# Detector.net
KiCad netlist of a schematic drawn in Altium Designer
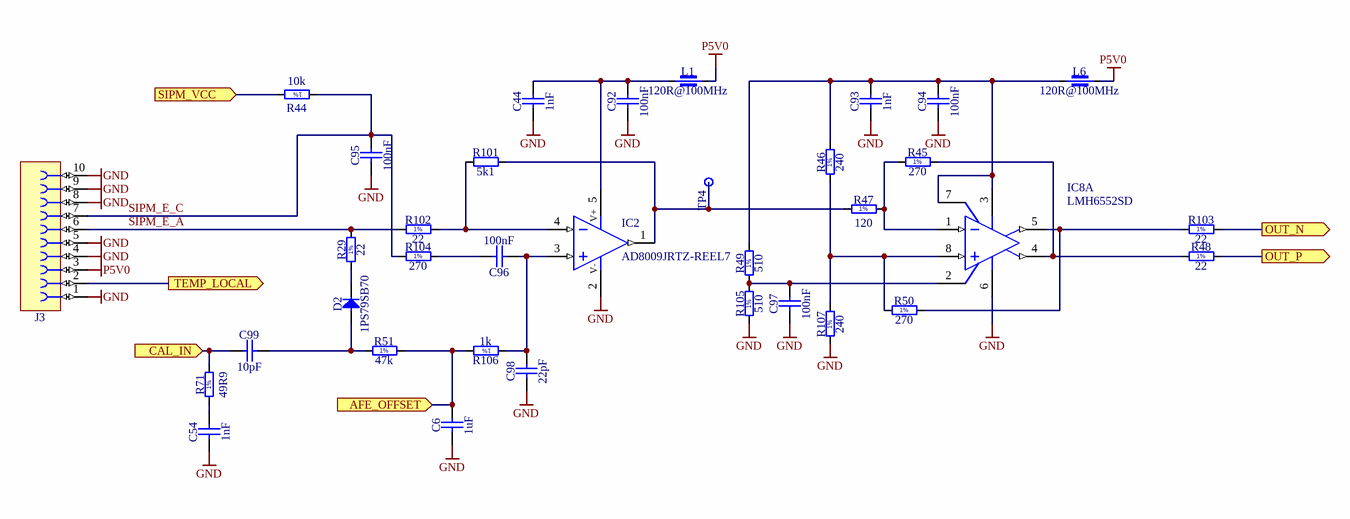
[diagram p0: Detector.SchDoc]

(export (version "E")
  (design (tool "Eeschema 10.0.6"))
  (components
    (comp (ref "C6")
      (value "1uF")
      (footprint "CAPC1608X87N")
      (description "Non-polarised capacitor")
      (fields
        (field (name "PART NUMBER") "CC0603_1UF_16V_10%_X7R")
        (field (name "VOLTAGE") "16V")
        (field (name "AUTHOR") "CERN DEM JLC")
      )
      (libsource (lib "Capacitors") (part "Capacitor - non polarized"))
    )
    (comp (ref "C44")
      (value "1nF")
      (footprint "CAPC1005X55N")
      (description "Non-polarised capacitor")
      (fields
        (field (name "PART NUMBER") "CC0402_1NF_50V_5%_C0G")
        (field (name "VOLTAGE") "50V")
        (field (name "AUTHOR") "CERN DEM BC")
      )
      (libsource (lib "Capacitors") (part "Capacitor - non polarized"))
    )
    (comp (ref "C54")
      (value "1nF")
      (footprint "CAPC1005X55N")
      (description "Non-polarised capacitor")
      (fields
        (field (name "PART NUMBER") "CC0402_1NF_50V_5%_C0G")
        (field (name "VOLTAGE") "50V")
        (field (name "AUTHOR") "CERN DEM BC")
      )
      (libsource (lib "Capacitors") (part "Capacitor - non polarized"))
    )
    (comp (ref "C92")
      (value "100nF")
      (footprint "CAPC1005X55N")
      (description "Non-polarised capacitor")
      (fields
        (field (name "PART NUMBER") "CC0402_100NF_16V_10%_X7R")
        (field (name "VOLTAGE") "16V")
        (field (name "AUTHOR") "CERN DEM JLC")
      )
      (libsource (lib "Capacitors") (part "Capacitor - non polarized"))
    )
    (comp (ref "C93")
      (value "1nF")
      (footprint "CAPC1005X55N")
      (description "Non-polarised capacitor")
      (fields
        (field (name "PART NUMBER") "CC0402_1NF_50V_5%_C0G")
        (field (name "VOLTAGE") "50V")
        (field (name "AUTHOR") "CERN DEM BC")
      )
      (libsource (lib "Capacitors") (part "Capacitor - non polarized"))
    )
    (comp (ref "C94")
      (value "100nF")
      (footprint "CAPC1005X55N")
      (description "Non-polarised capacitor")
      (fields
        (field (name "PART NUMBER") "CC0402_100NF_16V_10%_X7R")
        (field (name "VOLTAGE") "16V")
        (field (name "AUTHOR") "CERN DEM JLC")
      )
      (libsource (lib "Capacitors") (part "Capacitor - non polarized"))
    )
    (comp (ref "C95")
      (value "100nF")
      (footprint "CAPC1608X90N")
      (description "Non-polarised capacitor")
      (fields
        (field (name "PART NUMBER") "CC0603_100NF_100V_10%_X7R")
        (field (name "VOLTAGE") "100V")
        (field (name "AUTHOR") "CERN DEM JLC")
      )
      (libsource (lib "Capacitors") (part "Capacitor - non polarized"))
    )
    (comp (ref "C96")
      (value "100nF")
      (footprint "CAPC1608X90N")
      (description "Non-polarised capacitor")
      (fields
        (field (name "PART NUMBER") "CC0603_100NF_100V_10%_X7R")
        (field (name "VOLTAGE") "100V")
        (field (name "AUTHOR") "CERN DEM JLC")
      )
      (libsource (lib "Capacitors") (part "Capacitor - non polarized"))
    )
    (comp (ref "C97")
      (value "100nF")
      (footprint "CAPC1005X55N")
      (description "Non-polarised capacitor")
      (fields
        (field (name "PART NUMBER") "CC0402_100NF_16V_10%_X7R")
        (field (name "VOLTAGE") "16V")
        (field (name "AUTHOR") "CERN DEM JLC")
      )
      (libsource (lib "Capacitors") (part "Capacitor - non polarized"))
    )
    (comp (ref "C98")
      (value "22pF")
      (footprint "CAPC1005X55N")
      (description "Non-polarised capacitor")
      (fields
        (field (name "PART NUMBER") "CC0402_22PF_50V_5%_C0G")
        (field (name "VOLTAGE") "50V")
        (field (name "AUTHOR") "CERN DEM JLC")
      )
      (libsource (lib "Capacitors") (part "Capacitor - non polarized"))
    )
    (comp (ref "C99")
      (value "10pF")
      (footprint "CAPC1608X87N")
      (description "Non-polarised capacitor")
      (fields
        (field (name "PART NUMBER") "CC0603_10PF_50V_5%_NP0")
        (field (name "VOLTAGE") "50V")
        (field (name "AUTHOR") "CERN DEM JLC")
      )
      (libsource (lib "Capacitors") (part "Capacitor - non polarized"))
    )
    (comp (ref "D2")
      (value "1PS79SB70")
      (footprint "SODFL1608X65N")
      (description "Diode")
      (fields (field (name "VOLTAGE") "70V") (field (name "POWER") "70mA") (field (name "AUTHOR") "GK"))
      (libsource (lib "Diodes") (part "D_1PS79SB70"))
    )
    (comp (ref "IC2")
      (value "AD8009JRTZ-REEL7")
      (footprint "SOT95P280X145-5N")
      (description "Operational Amplifier")
      (fields (field (name "MANUFACTURER") "ANALOG DEVICES") (field (name "AUTHOR") "CERN DEM JLC"))
      (libsource (lib "ICs And Semiconductors") (part "Operational Amplifier Type7"))
    )
    (comp (ref "IC8")
      (value "LMH6552SD")
      (footprint "SDA08C")
      (description "1.5 GHz Fully Differential Amplifier, 8-pin LLP")
      (fields (field (name "MANUFACTURER") "National Semiconductor"))
      (libsource (lib "Altium Content Vault") (part "AMP-DIFA-LMH6552-9"))
    )
    (comp (ref "J3")
      (value "FFC/FPC")
      (footprint "MOLEX_52745-1097")
      (description "Connector 10 Female")
      (fields
        (field (name "PART NUMBER") "MOLEX_52745-1097")
        (field (name "MANUFACTURER") "MOLEX")
        (field (name "AUTHOR") "CERN DEM JLC")
      )
      (libsource (lib "Connectors") (part "Connector 10 Female"))
    )
    (comp (ref "L1")
      (value "120R@100MHz")
      (footprint "INDC1005X55N")
      (fields
        (field (name "PART NUMBER") "IND0402_MURATA_BLM15PX121SN1D")
        (field (name "POWER") "2A")
        (field (name "TOLERANCE") "±25%")
        (field (name "AUTHOR") "CERN DEM JMW")
      )
      (libsource (lib "Inductors & Transformers") (part "Ferrite Bead"))
    )
    (comp (ref "L6")
      (value "120R@100MHz")
      (footprint "INDC1005X55N")
      (fields
        (field (name "PART NUMBER") "IND0402_MURATA_BLM15PX121SN1D")
        (field (name "POWER") "2A")
        (field (name "TOLERANCE") "±25%")
        (field (name "AUTHOR") "CERN DEM JMW")
      )
      (libsource (lib "Inductors & Transformers") (part "Ferrite Bead"))
    )
    (comp (ref "R29")
      (value "22")
      (footprint "RESC1608X55N")
      (description "Resistor - 1%")
      (fields
        (field (name "PART NUMBER") "R0603_22R_1%_0.1W_100PPM")
        (field (name "POWER") "0.1W")
        (field (name "AUTHOR") "CERN DEM JLC")
      )
      (libsource (lib "Resistors") (part "Resistor - 1%"))
    )
    (comp (ref "R44")
      (value "10k")
      (footprint "RESC1005X40N")
      (description "Resistor - 1%")
      (fields
        (field (name "PART NUMBER") "R0402_10K_1%_0.0625W_100PPM")
        (field (name "POWER") "0.0625W")
        (field (name "AUTHOR") "CERN DEM JLC")
      )
      (libsource (lib "Resistors") (part "Resistor - 1%"))
    )
    (comp (ref "R45")
      (value "270")
      (footprint "RESC1005X40N")
      (description "Resistor - 1%")
      (fields
        (field (name "PART NUMBER") "R0402_270R_1%_0.0625W_100PPM")
        (field (name "POWER") "0.0625W")
        (field (name "AUTHOR") "CERN DEM JLC")
      )
      (libsource (lib "Resistors") (part "Resistor - 1%"))
    )
    (comp (ref "R46")
      (value "240")
      (footprint "RESC1005X40N")
      (description "Resistor - 1%")
      (fields
        (field (name "PART NUMBER") "R0402_240R_1%_0.0625W_100PPM")
        (field (name "POWER") "0.0625W")
        (field (name "AUTHOR") "CERN DEM JLC")
      )
      (libsource (lib "Resistors") (part "Resistor - 1%"))
    )
    (comp (ref "R47")
      (value "120")
      (footprint "RESC1005X40N")
      (description "Resistor - 1%")
      (fields
        (field (name "PART NUMBER") "R0402_120R_1%_0.0625W_100PPM")
        (field (name "POWER") "0.0625W")
        (field (name "AUTHOR") "CERN DEM JLC")
      )
      (libsource (lib "Resistors") (part "Resistor - 1%"))
    )
    (comp (ref "R48")
      (value "22")
      (footprint "RESC1608X55N")
      (description "Resistor - 1%")
      (fields
        (field (name "PART NUMBER") "R0603_22R_1%_0.1W_100PPM")
        (field (name "POWER") "0.1W")
        (field (name "AUTHOR") "CERN DEM JLC")
      )
      (libsource (lib "Resistors") (part "Resistor - 1%"))
    )
    (comp (ref "R49")
      (value "510")
      (footprint "RESC1005X40N")
      (description "Resistor - 1%")
      (fields
        (field (name "PART NUMBER") "R0402_510R_1%_0.0625W_100PPM")
        (field (name "POWER") "0.0625W")
        (field (name "AUTHOR") "CERN DEM JLC")
      )
      (libsource (lib "Resistors") (part "Resistor - 1%"))
    )
    (comp (ref "R50")
      (value "270")
      (footprint "RESC1005X40N")
      (description "Resistor - 1%")
      (fields
        (field (name "PART NUMBER") "R0402_270R_1%_0.0625W_100PPM")
        (field (name "POWER") "0.0625W")
        (field (name "AUTHOR") "CERN DEM JLC")
      )
      (libsource (lib "Resistors") (part "Resistor - 1%"))
    )
    (comp (ref "R51")
      (value "47k")
      (footprint "RESC1005X40N")
      (description "Resistor - 1%")
      (fields
        (field (name "PART NUMBER") "R0402_47K_1%_0.0625W_100PPM")
        (field (name "POWER") "0.0625W")
        (field (name "AUTHOR") "CERN DEM JLC")
      )
      (libsource (lib "Resistors") (part "Resistor - 1%"))
    )
    (comp (ref "R71")
      (value "49R9")
      (footprint "RESC1005X40N")
      (description "Resistor - 1%")
      (fields
        (field (name "PART NUMBER") "R0402_49R9_1%_0.0625W_100PPM")
        (field (name "POWER") "0.0625W")
        (field (name "AUTHOR") "CERN DEM JLC")
      )
      (libsource (lib "Resistors") (part "Resistor - 1%"))
    )
    (comp (ref "R101")
      (value "5k1")
      (footprint "RESC1005X40N")
      (description "Resistor - 1%")
      (fields
        (field (name "PART NUMBER") "R0402_5K1_1%_0.0625W_100PPM")
        (field (name "POWER") "0.0625W")
        (field (name "AUTHOR") "CERN DEM JLC")
      )
      (libsource (lib "") (part "Resistor - 1%_1"))
    )
    (comp (ref "R102")
      (value "22")
      (footprint "RESC1608X55N")
      (description "Resistor - 1%")
      (fields
        (field (name "PART NUMBER") "R0603_22R_1%_0.1W_100PPM")
        (field (name "POWER") "0.1W")
        (field (name "AUTHOR") "CERN DEM JLC")
      )
      (libsource (lib "Resistors") (part "Resistor - 1%"))
    )
    (comp (ref "R103")
      (value "22")
      (footprint "RESC1608X55N")
      (description "Resistor - 1%")
      (fields
        (field (name "PART NUMBER") "R0603_22R_1%_0.1W_100PPM")
        (field (name "POWER") "0.1W")
        (field (name "AUTHOR") "CERN DEM JLC")
      )
      (libsource (lib "Resistors") (part "Resistor - 1%"))
    )
    (comp (ref "R104")
      (value "270")
      (footprint "RESC1005X40N")
      (description "Resistor - 1%")
      (fields
        (field (name "PART NUMBER") "R0402_270R_1%_0.0625W_100PPM")
        (field (name "POWER") "0.0625W")
        (field (name "AUTHOR") "CERN DEM JLC")
      )
      (libsource (lib "Resistors") (part "Resistor - 1%"))
    )
    (comp (ref "R105")
      (value "510")
      (footprint "RESC1005X40N")
      (description "Resistor - 1%")
      (fields
        (field (name "PART NUMBER") "R0402_510R_1%_0.0625W_100PPM")
        (field (name "POWER") "0.0625W")
        (field (name "AUTHOR") "CERN DEM JLC")
      )
      (libsource (lib "Resistors") (part "Resistor - 1%"))
    )
    (comp (ref "R106")
      (value "1k")
      (footprint "RESC1005X40N")
      (description "Resistor - 1%")
      (fields
        (field (name "PART NUMBER") "R0402_1K_1%_0.0625W_100PPM")
        (field (name "POWER") "0.0625W")
        (field (name "AUTHOR") "CERN DEM JLC")
      )
      (libsource (lib "Resistors") (part "Resistor - 1%"))
    )
    (comp (ref "R107")
      (value "240")
      (footprint "RESC1005X40N")
      (description "Resistor - 1%")
      (fields
        (field (name "PART NUMBER") "R0402_240R_1%_0.0625W_100PPM")
        (field (name "POWER") "0.0625W")
        (field (name "AUTHOR") "CERN DEM JLC")
      )
      (libsource (lib "Resistors") (part "Resistor - 1%"))
    )
    (comp (ref "TP4")
      (value "Test Point")
      (footprint "TPS127")
      (fields (field (name "PART NUMBER") "SMD_PAD_1.27X1.27MM") (field (name "AUTHOR") "CERN DEM JLC"))
      (libsource (lib "Eletro-mechanical") (part "Test Point"))
    )
  )
  (nets
    (net (code "1") (name "/AFE_OFFSET") (class "Default")
      (node (ref "C6") (pin "2") (pinfunction "2_2") (pintype "passive"))
      (node (ref "R106") (pin "2") (pinfunction "2_2") (pintype "passive"))
      (node (ref "R51") (pin "2") (pinfunction "2_2") (pintype "passive"))
    )
    (net (code "2") (name "/CAL_IN") (class "Default")
      (node (ref "C99") (pin "1") (pinfunction "1_1") (pintype "passive"))
      (node (ref "R71") (pin "2") (pinfunction "2_2") (pintype "passive"))
    )
    (net (code "3") (name "/OUT_N") (class "Default")
      (node (ref "R103") (pin "2") (pinfunction "2_2") (pintype "passive"))
    )
    (net (code "4") (name "/OUT_P") (class "Default")
      (node (ref "R48") (pin "2") (pinfunction "2_2") (pintype "passive"))
    )
    (net (code "5") (name "/SIPM_E_A") (class "Default")
      (node (ref "J3") (pin "6") (pinfunction "6_6") (pintype "bidirectional"))
      (node (ref "R102") (pin "1") (pinfunction "1_1") (pintype "passive"))
      (node (ref "R29") (pin "2") (pinfunction "2_2") (pintype "passive"))
    )
    (net (code "6") (name "/SIPM_E_C") (class "Default")
      (node (ref "C95") (pin "2") (pinfunction "2_2") (pintype "passive"))
      (node (ref "J3") (pin "7") (pinfunction "7_7") (pintype "bidirectional"))
      (node (ref "R104") (pin "1") (pinfunction "1_1") (pintype "passive"))
      (node (ref "R44") (pin "1") (pinfunction "1_1") (pintype "passive"))
    )
    (net (code "7") (name "/SIPM_VCC") (class "Default")
      (node (ref "R44") (pin "2") (pinfunction "2_2") (pintype "passive"))
    )
    (net (code "8") (name "/TEMP_LOCAL") (class "Default")
      (node (ref "J3") (pin "2") (pinfunction "2_2") (pintype "bidirectional"))
    )
    (net (code "9") (name "GND") (class "Default")
      (node (ref "C44") (pin "1") (pinfunction "1_1") (pintype "passive"))
      (node (ref "C54") (pin "1") (pinfunction "1_1") (pintype "passive"))
      (node (ref "C6") (pin "1") (pinfunction "1_1") (pintype "passive"))
      (node (ref "C92") (pin "1") (pinfunction "1_1") (pintype "passive"))
      (node (ref "C93") (pin "1") (pinfunction "1_1") (pintype "passive"))
      (node (ref "C94") (pin "1") (pinfunction "1_1") (pintype "passive"))
      (node (ref "C95") (pin "1") (pinfunction "1_1") (pintype "passive"))
      (node (ref "C97") (pin "1") (pinfunction "1_1") (pintype "passive"))
      (node (ref "C98") (pin "1") (pinfunction "1_1") (pintype "passive"))
      (node (ref "IC2") (pin "2") (pinfunction "V-_2") (pintype "power_in"))
      (node (ref "IC8") (pin "6") (pinfunction "V-_6") (pintype "power_in"))
      (node (ref "J3") (pin "1") (pinfunction "1_1") (pintype "bidirectional"))
      (node (ref "J3") (pin "10") (pinfunction "10_10") (pintype "bidirectional"))
      (node (ref "J3") (pin "4") (pinfunction "4_4") (pintype "bidirectional"))
      (node (ref "J3") (pin "5") (pinfunction "5_5") (pintype "bidirectional"))
      (node (ref "J3") (pin "8") (pinfunction "8_8") (pintype "bidirectional"))
      (node (ref "J3") (pin "9") (pinfunction "9_9") (pintype "bidirectional"))
      (node (ref "R105") (pin "1") (pinfunction "1_1") (pintype "passive"))
      (node (ref "R107") (pin "1") (pinfunction "1_1") (pintype "passive"))
    )
    (net (code "10") (name "Net-(C54-Pad2)") (class "Default")
      (node (ref "C54") (pin "2") (pinfunction "2_2") (pintype "passive"))
      (node (ref "R71") (pin "1") (pinfunction "1_1") (pintype "passive"))
    )
    (net (code "11") (name "Net-(C96-Pad2)") (class "Default")
      (node (ref "C96") (pin "2") (pinfunction "2_2") (pintype "passive"))
      (node (ref "R104") (pin "2") (pinfunction "2_2") (pintype "passive"))
    )
    (net (code "12") (name "Net-(D2-A)") (class "Default")
      (node (ref "C99") (pin "2") (pinfunction "2_2") (pintype "passive"))
      (node (ref "D2") (pin "2") (pinfunction "A_2") (pintype "passive"))
      (node (ref "R51") (pin "1") (pinfunction "1_1") (pintype "passive"))
    )
    (net (code "13") (name "Net-(D2-C)") (class "Default")
      (node (ref "D2") (pin "1") (pinfunction "C_1") (pintype "passive"))
      (node (ref "R29") (pin "1") (pinfunction "1_1") (pintype "passive"))
    )
    (net (code "14") (name "Net-(IC2-IN+)") (class "Default")
      (node (ref "C96") (pin "1") (pinfunction "1_1") (pintype "passive"))
      (node (ref "C98") (pin "2") (pinfunction "2_2") (pintype "passive"))
      (node (ref "IC2") (pin "3") (pinfunction "IN+_3") (pintype "input"))
      (node (ref "R106") (pin "1") (pinfunction "1_1") (pintype "passive"))
    )
    (net (code "15") (name "Net-(IC2-IN-)") (class "Default")
      (node (ref "IC2") (pin "4") (pinfunction "IN-_4") (pintype "input"))
      (node (ref "R101") (pin "1") (pinfunction "1_1") (pintype "passive"))
      (node (ref "R102") (pin "2") (pinfunction "2_2") (pintype "passive"))
    )
    (net (code "16") (name "Net-(IC2-OUT)") (class "Default")
      (node (ref "IC2") (pin "1") (pinfunction "OUT_1") (pintype "output"))
      (node (ref "R101") (pin "2") (pinfunction "2_2") (pintype "passive"))
      (node (ref "R47") (pin "1") (pinfunction "1_1") (pintype "passive"))
      (node (ref "TP4") (pin "1") (pinfunction "1_1") (pintype "bidirectional"))
    )
    (net (code "17") (name "Net-(IC2-V+)") (class "Default")
      (node (ref "C44") (pin "2") (pinfunction "2_2") (pintype "passive"))
      (node (ref "C92") (pin "2") (pinfunction "2_2") (pintype "passive"))
      (node (ref "IC2") (pin "5") (pinfunction "V+_5") (pintype "power_in"))
      (node (ref "L1") (pin "1") (pinfunction "1_1") (pintype "passive"))
    )
    (net (code "18") (name "Net-(IC8A-EN)") (class "Default")
      (node (ref "C93") (pin "2") (pinfunction "2_2") (pintype "passive"))
      (node (ref "C94") (pin "2") (pinfunction "2_2") (pintype "passive"))
      (node (ref "IC8") (pin "3") (pinfunction "V+_3") (pintype "power_in"))
      (node (ref "IC8") (pin "7") (pinfunction "EN_7") (pintype "passive"))
      (node (ref "L6") (pin "1") (pinfunction "1_1") (pintype "passive"))
      (node (ref "R46") (pin "2") (pinfunction "2_2") (pintype "passive"))
      (node (ref "R49") (pin "2") (pinfunction "2_2") (pintype "passive"))
    )
    (net (code "19") (name "Net-(IC8A-IN+)") (class "Default")
      (node (ref "IC8") (pin "8") (pinfunction "IN+_8") (pintype "input"))
      (node (ref "R107") (pin "2") (pinfunction "2_2") (pintype "passive"))
      (node (ref "R46") (pin "1") (pinfunction "1_1") (pintype "passive"))
      (node (ref "R50") (pin "1") (pinfunction "1_1") (pintype "passive"))
    )
    (net (code "20") (name "Net-(IC8A-IN-)") (class "Default")
      (node (ref "IC8") (pin "1") (pinfunction "IN-_1") (pintype "input"))
      (node (ref "R45") (pin "1") (pinfunction "1_1") (pintype "passive"))
      (node (ref "R47") (pin "2") (pinfunction "2_2") (pintype "passive"))
    )
    (net (code "21") (name "Net-(IC8A-OUT+)") (class "Default")
      (node (ref "IC8") (pin "4") (pinfunction "OUT+_4") (pintype "output"))
      (node (ref "R45") (pin "2") (pinfunction "2_2") (pintype "passive"))
      (node (ref "R48") (pin "1") (pinfunction "1_1") (pintype "passive"))
    )
    (net (code "22") (name "Net-(IC8A-OUT-)") (class "Default")
      (node (ref "IC8") (pin "5") (pinfunction "OUT-_5") (pintype "output"))
      (node (ref "R103") (pin "1") (pinfunction "1_1") (pintype "passive"))
      (node (ref "R50") (pin "2") (pinfunction "2_2") (pintype "passive"))
    )
    (net (code "23") (name "Net-(IC8A-VCM)") (class "Default")
      (node (ref "C97") (pin "2") (pinfunction "2_2") (pintype "passive"))
      (node (ref "IC8") (pin "2") (pinfunction "VCM_2") (pintype "passive"))
      (node (ref "R105") (pin "2") (pinfunction "2_2") (pintype "passive"))
      (node (ref "R49") (pin "1") (pinfunction "1_1") (pintype "passive"))
    )
    (net (code "24") (name "P5V0") (class "Default")
      (node (ref "J3") (pin "3") (pinfunction "3_3") (pintype "bidirectional"))
      (node (ref "L1") (pin "2") (pinfunction "2_2") (pintype "passive"))
      (node (ref "L6") (pin "2") (pinfunction "2_2") (pintype "passive"))
    )
  )
)
